# FLYTE-v1.net
KiCad netlist of a schematic drawn in EAGLE
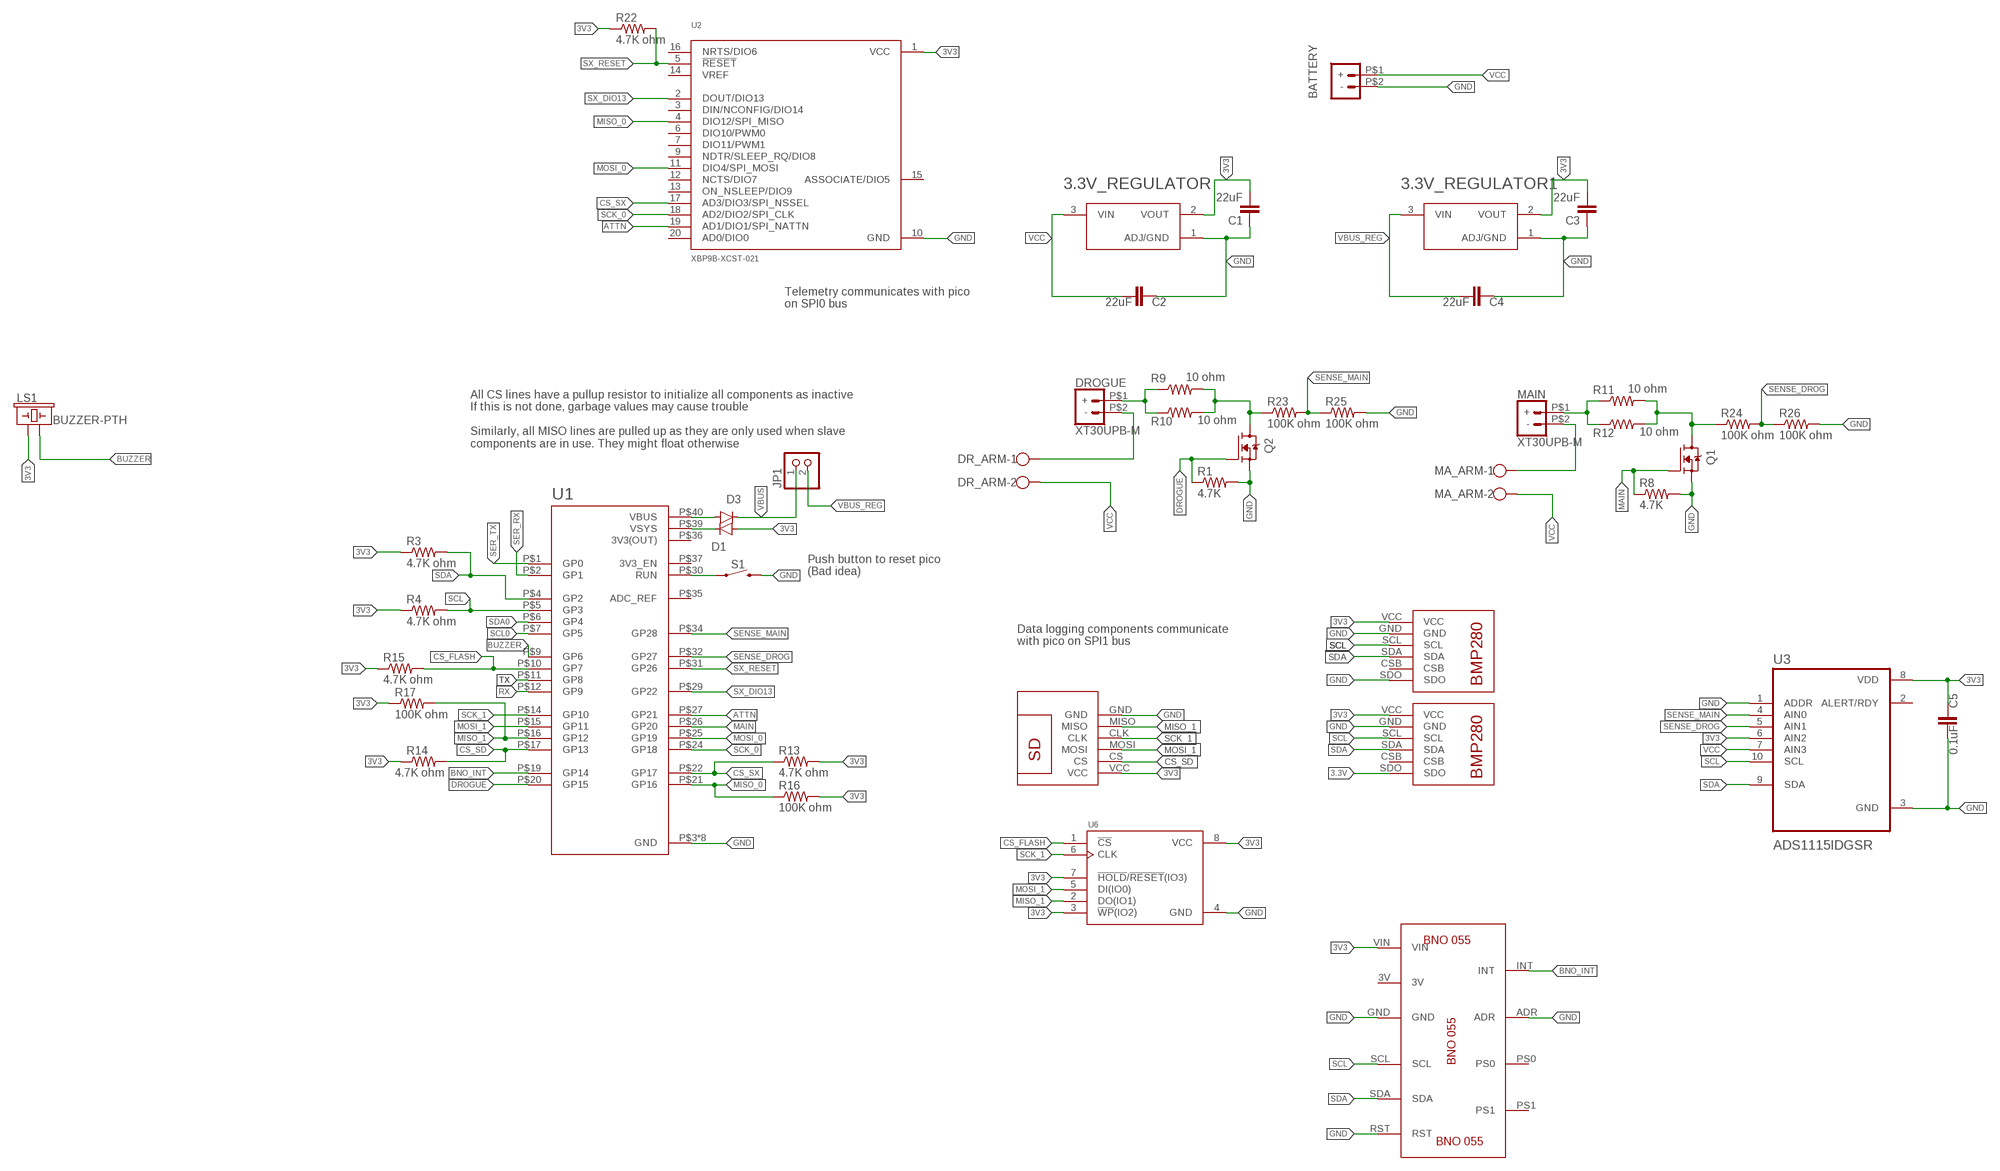
[diagram p0: schematic, sheet 1]

(export (version "E")
  (design (tool "Eeschema 10.0.6"))
  (components
    (comp (ref "3.3V_REGULATOR")
      (value "AMS1117-3.3")
      (footprint "eagle-import:SOT229P700X180-4N")
      (fields (field (name "MF") "Advanced Monolithic Systems"))
      (libsource (lib "eagle-import") (part "AMS1117-3.3"))
    )
    (comp (ref "3.3V_REGULATOR1")
      (value "AMS1117-3.3")
      (footprint "eagle-import:SOT229P700X180-4N")
      (fields (field (name "MF") "Advanced Monolithic Systems"))
      (libsource (lib "eagle-import") (part "AMS1117-3.3"))
    )
    (comp (ref "BATTERY")
      (value "XT30UPB-M")
      (footprint "eagle-import:XT30UPB-M")
      (fields (field (name "MF") "amass"))
      (libsource (lib "eagle-import") (part "XT30UPB-M"))
    )
    (comp (ref "C1")
      (value "22uF")
      (footprint "eagle-import:0805")
      (libsource (lib "eagle-import") (part "22UF-0805-6.3V-20%"))
    )
    (comp (ref "C2")
      (value "22uF")
      (footprint "eagle-import:0805")
      (libsource (lib "eagle-import") (part "22UF-0805-6.3V-20%"))
    )
    (comp (ref "C3")
      (value "22uF")
      (footprint "eagle-import:0805")
      (libsource (lib "eagle-import") (part "22UF-0805-6.3V-20%"))
    )
    (comp (ref "C4")
      (value "22uF")
      (footprint "eagle-import:0805")
      (libsource (lib "eagle-import") (part "22UF-0805-6.3V-20%"))
    )
    (comp (ref "C5")
      (value "0.1uF")
      (footprint "eagle-import:0805")
      (libsource (lib "eagle-import") (part "22UF-0805-6.3V-20%"))
    )
    (comp (ref "D1")
      (value "1N4004")
      (footprint "eagle-import:DO41-10")
      (libsource (lib "eagle-import") (part "1N4004"))
    )
    (comp (ref "D3")
      (value "1N4004")
      (footprint "eagle-import:DO41-10")
      (libsource (lib "eagle-import") (part "1N4004"))
    )
    (comp (ref "DROGUE")
      (value "XT30UPB-M")
      (footprint "eagle-import:XT30UPB-M")
      (fields (field (name "MF") "amass"))
      (libsource (lib "eagle-import") (part "XT30UPB-M"))
    )
    (comp (ref "DR_ARM")
      (value "W237-102")
      (footprint "eagle-import:W237-102")
      (fields (field (name "MPN") "237-102"))
      (libsource (lib "eagle-import") (part "W237-102"))
    )
    (comp (ref "JP1")
      (value "PINHD-1X2")
      (footprint "eagle-import:1X02")
      (libsource (lib "eagle-import") (part "PINHD-1X2"))
    )
    (comp (ref "LS1")
      (value "BUZZER-PTH")
      (footprint "eagle-import:BUZZER-12MM")
      (libsource (lib "eagle-import") (part "BUZZER-PTH"))
    )
    (comp (ref "MAIN")
      (value "XT30UPB-M")
      (footprint "eagle-import:XT30UPB-M")
      (fields (field (name "MF") "amass"))
      (libsource (lib "eagle-import") (part "XT30UPB-M"))
    )
    (comp (ref "MA_ARM")
      (value "W237-102")
      (footprint "eagle-import:W237-102")
      (fields (field (name "MPN") "237-102"))
      (libsource (lib "eagle-import") (part "W237-102"))
    )
    (comp (ref "Q1")
      (value "IRF540NPBF")
      (footprint "eagle-import:TO254P1054X469X1930-3")
      (fields (field (name "MF") "Infineon"))
      (libsource (lib "eagle-import") (part "IRF540NPBF"))
    )
    (comp (ref "Q2")
      (value "IRF540NPBF")
      (footprint "eagle-import:TO254P1054X469X1930-3")
      (fields (field (name "MF") "Infineon"))
      (libsource (lib "eagle-import") (part "IRF540NPBF"))
    )
    (comp (ref "R1")
      (value "4.7K")
      (footprint "eagle-import:R0805")
      (libsource (lib "eagle-import") (part "R-US_R0805"))
    )
    (comp (ref "R3")
      (value "4.7K ohm")
      (footprint "eagle-import:R0805")
      (libsource (lib "eagle-import") (part "R-US_R0805"))
    )
    (comp (ref "R4")
      (value "4.7K ohm")
      (footprint "eagle-import:R0805")
      (libsource (lib "eagle-import") (part "R-US_R0805"))
    )
    (comp (ref "R8")
      (value "4.7K")
      (footprint "eagle-import:R0805")
      (libsource (lib "eagle-import") (part "R-US_R0805"))
    )
    (comp (ref "R9")
      (value "10 ohm")
      (footprint "eagle-import:0207_10")
      (libsource (lib "eagle-import") (part "R-US_0207/10"))
    )
    (comp (ref "R10")
      (value "10 ohm")
      (footprint "eagle-import:0207_10")
      (libsource (lib "eagle-import") (part "R-US_0207/10"))
    )
    (comp (ref "R11")
      (value "10 ohm")
      (footprint "eagle-import:0207_10")
      (libsource (lib "eagle-import") (part "R-US_0207/10"))
    )
    (comp (ref "R12")
      (value "10 ohm")
      (footprint "eagle-import:0207_10")
      (libsource (lib "eagle-import") (part "R-US_0207/10"))
    )
    (comp (ref "R13")
      (value "4.7K ohm")
      (footprint "eagle-import:R0805")
      (libsource (lib "eagle-import") (part "R-US_R0805"))
    )
    (comp (ref "R14")
      (value "4.7K ohm")
      (footprint "eagle-import:R0805")
      (libsource (lib "eagle-import") (part "R-US_R0805"))
    )
    (comp (ref "R15")
      (value "4.7K ohm")
      (footprint "eagle-import:R0805")
      (libsource (lib "eagle-import") (part "R-US_R0805"))
    )
    (comp (ref "R16")
      (value "100K ohm")
      (footprint "eagle-import:R0805")
      (libsource (lib "eagle-import") (part "R-US_R0805"))
    )
    (comp (ref "R17")
      (value "100K ohm")
      (footprint "eagle-import:R0805")
      (libsource (lib "eagle-import") (part "R-US_R0805"))
    )
    (comp (ref "R22")
      (value "4.7K ohm")
      (footprint "eagle-import:R0805")
      (libsource (lib "eagle-import") (part "R-US_R0805"))
    )
    (comp (ref "R23")
      (value "100K ohm")
      (footprint "eagle-import:R0805")
      (libsource (lib "eagle-import") (part "R-US_R0805"))
    )
    (comp (ref "R24")
      (value "100K ohm")
      (footprint "eagle-import:R0805")
      (libsource (lib "eagle-import") (part "R-US_R0805"))
    )
    (comp (ref "R25")
      (value "100K ohm")
      (footprint "eagle-import:R0805")
      (libsource (lib "eagle-import") (part "R-US_R0805"))
    )
    (comp (ref "R26")
      (value "100K ohm")
      (footprint "eagle-import:R0805")
      (libsource (lib "eagle-import") (part "R-US_R0805"))
    )
    (comp (ref "S1")
      (value "MOMENTARY-SWITCH-SPST-PTH-6.0MM")
      (footprint "eagle-import:TACTILE_SWITCH_PTH_6.0MM")
      (libsource (lib "eagle-import") (part "MOMENTARY-SWITCH-SPST-PTH-6.0MM"))
    )
    (comp (ref "U$1")
      (value "BMP280")
      (footprint "eagle-import:BMP280")
      (libsource (lib "eagle-import") (part "BMP280"))
    )
    (comp (ref "U$2")
      (value "BMP280")
      (footprint "eagle-import:BMP280")
      (libsource (lib "eagle-import") (part "BMP280"))
    )
    (comp (ref "U$3")
      (value "SDREADER")
      (footprint "eagle-import:SDREADER")
      (libsource (lib "eagle-import") (part "SDREADER"))
    )
    (comp (ref "U$4")
      (value "BNO055")
      (footprint "eagle-import:BNO055")
      (libsource (lib "eagle-import") (part "BNO055"))
    )
    (comp (ref "U1")
      (value "RASPBERRY_PICO-NO_DEBUG")
      (footprint "eagle-import:PICO-PKG-NO_DEBUG")
      (libsource (lib "eagle-import") (part "RASPBERRY_PICO-NO_DEBUG"))
    )
    (comp (ref "U2")
      (value "XBP9B-XCST-021")
      (footprint "eagle-import:DIP2200W51P200L3294H279Q20P")
      (fields (field (name "MF") "Digi International"))
      (libsource (lib "eagle-import") (part "XBP9B-XCST-021"))
    )
    (comp (ref "U3")
      (value "ADS1115IDGSR")
      (footprint "eagle-import:SOP50P490X110-10N")
      (fields (field (name "MF") "Texas Instruments"))
      (libsource (lib "eagle-import") (part "ADS1115IDGSR"))
    )
    (comp (ref "U6")
      (value "W25Q32JVSSIQ")
      (footprint "eagle-import:SOIC127P790X216-8N")
      (fields (field (name "MF") "Winbond"))
      (libsource (lib "eagle-import") (part "W25Q32JVSSIQ"))
    )
  )
  (nets
    (net (code "1") (name "/3V3(OUT)") (class "Default")
      (node (ref "U1") (pin "P$36") (pinfunction "3V3(OUT)_P$36") (pintype "power_in"))
    )
    (net (code "2") (name "3.3V") (class "Default")
      (node (ref "U$2") (pin "SDO") (pinfunction "SDO_SDO") (pintype "bidirectional"))
    )
    (net (code "3") (name "3V3") (class "Default")
      (node (ref "3.3V_REGULATOR") (pin "2") (pinfunction "VOUT_2") (pintype "output"))
      (node (ref "3.3V_REGULATOR1") (pin "2") (pinfunction "VOUT_2") (pintype "output"))
      (node (ref "C1") (pin "2") (pinfunction "2_2") (pintype "passive"))
      (node (ref "C3") (pin "2") (pinfunction "2_2") (pintype "passive"))
      (node (ref "C5") (pin "1") (pinfunction "1_1") (pintype "passive"))
      (node (ref "D1") (pin "A") (pinfunction "A_A") (pintype "passive"))
      (node (ref "LS1") (pin "+") (pinfunction "1_+") (pintype "passive"))
      (node (ref "R13") (pin "2") (pinfunction "2_2") (pintype "passive"))
      (node (ref "R14") (pin "1") (pinfunction "1_1") (pintype "passive"))
      (node (ref "R15") (pin "1") (pinfunction "1_1") (pintype "passive"))
      (node (ref "R16") (pin "2") (pinfunction "2_2") (pintype "passive"))
      (node (ref "R17") (pin "1") (pinfunction "1_1") (pintype "passive"))
      (node (ref "R22") (pin "1") (pinfunction "1_1") (pintype "passive"))
      (node (ref "R3") (pin "1") (pinfunction "1_1") (pintype "passive"))
      (node (ref "R4") (pin "1") (pinfunction "1_1") (pintype "passive"))
      (node (ref "U$1") (pin "VCC") (pinfunction "VCC_VCC") (pintype "bidirectional"))
      (node (ref "U$2") (pin "VCC") (pinfunction "VCC_VCC") (pintype "bidirectional"))
      (node (ref "U$3") (pin "VCC") (pinfunction "VCC_VCC") (pintype "bidirectional"))
      (node (ref "U$4") (pin "VIN") (pinfunction "VIN_VIN") (pintype "bidirectional"))
      (node (ref "U2") (pin "1") (pinfunction "VCC_1") (pintype "power_in"))
      (node (ref "U3") (pin "6") (pinfunction "AIN2_6") (pintype "input"))
      (node (ref "U3") (pin "8") (pinfunction "VDD_8") (pintype "power_in"))
      (node (ref "U6") (pin "3") (pinfunction "~{WP}(IO2)_3") (pintype "bidirectional"))
      (node (ref "U6") (pin "7") (pinfunction "~{HOLD}/~{RESET}(IO3)_7") (pintype "bidirectional"))
      (node (ref "U6") (pin "8") (pinfunction "VCC_8") (pintype "power_in"))
    )
    (net (code "4") (name "ATTN") (class "Default")
      (node (ref "U1") (pin "P$27") (pinfunction "GP21_P$27") (pintype "bidirectional"))
      (node (ref "U2") (pin "19") (pinfunction "AD1/DIO1/SPI_NATTN_19") (pintype "bidirectional"))
    )
    (net (code "5") (name "BNO_INT") (class "Default")
      (node (ref "U$4") (pin "INT") (pinfunction "INT_INT") (pintype "bidirectional"))
      (node (ref "U1") (pin "P$19") (pinfunction "GP14_P$19") (pintype "bidirectional"))
    )
    (net (code "6") (name "BUZZER") (class "Default")
      (node (ref "LS1") (pin "-") (pinfunction "2_-") (pintype "passive"))
      (node (ref "U1") (pin "P$9") (pinfunction "GP6_P$9") (pintype "bidirectional"))
    )
    (net (code "7") (name "CS_FLASH") (class "Default")
      (node (ref "R15") (pin "2") (pinfunction "2_2") (pintype "passive"))
      (node (ref "U1") (pin "P$10") (pinfunction "GP7_P$10") (pintype "bidirectional"))
      (node (ref "U6") (pin "1") (pinfunction "~{CS}_1") (pintype "input"))
    )
    (net (code "8") (name "CS_SD") (class "Default")
      (node (ref "R14") (pin "2") (pinfunction "2_2") (pintype "passive"))
      (node (ref "U$3") (pin "CS") (pinfunction "CS_CS") (pintype "bidirectional"))
      (node (ref "U1") (pin "P$17") (pinfunction "GP13_P$17") (pintype "bidirectional"))
    )
    (net (code "9") (name "CS_SX") (class "Default")
      (node (ref "R13") (pin "1") (pinfunction "1_1") (pintype "passive"))
      (node (ref "U1") (pin "P$22") (pinfunction "GP17_P$22") (pintype "bidirectional"))
      (node (ref "U2") (pin "17") (pinfunction "AD3/DIO3/SPI_NSSEL_17") (pintype "bidirectional"))
    )
    (net (code "10") (name "DROGUE") (class "Default")
      (node (ref "Q2") (pin "1") (pinfunction "G_1") (pintype "passive"))
      (node (ref "R1") (pin "1") (pinfunction "1_1") (pintype "passive"))
      (node (ref "U1") (pin "P$20") (pinfunction "GP15_P$20") (pintype "bidirectional"))
    )
    (net (code "11") (name "GND") (class "Default")
      (node (ref "3.3V_REGULATOR") (pin "1") (pinfunction "ADJ/GND_1") (pintype "power_in"))
      (node (ref "3.3V_REGULATOR1") (pin "1") (pinfunction "ADJ/GND_1") (pintype "power_in"))
      (node (ref "BATTERY") (pin "P$2") (pinfunction "-_P$2") (pintype "passive"))
      (node (ref "C1") (pin "1") (pinfunction "1_1") (pintype "passive"))
      (node (ref "C2") (pin "1") (pinfunction "1_1") (pintype "passive"))
      (node (ref "C3") (pin "1") (pinfunction "1_1") (pintype "passive"))
      (node (ref "C4") (pin "1") (pinfunction "1_1") (pintype "passive"))
      (node (ref "C5") (pin "2") (pinfunction "2_2") (pintype "passive"))
      (node (ref "Q1") (pin "3") (pinfunction "S_3") (pintype "passive"))
      (node (ref "Q2") (pin "3") (pinfunction "S_3") (pintype "passive"))
      (node (ref "R1") (pin "2") (pinfunction "2_2") (pintype "passive"))
      (node (ref "R25") (pin "2") (pinfunction "2_2") (pintype "passive"))
      (node (ref "R26") (pin "2") (pinfunction "2_2") (pintype "passive"))
      (node (ref "R8") (pin "2") (pinfunction "2_2") (pintype "passive"))
      (node (ref "S1") (pin "3") (pinfunction "2_3") (pintype "passive"))
      (node (ref "U$1") (pin "GND") (pinfunction "GND_GND") (pintype "bidirectional"))
      (node (ref "U$1") (pin "SDO") (pinfunction "SDO_SDO") (pintype "bidirectional"))
      (node (ref "U$2") (pin "GND") (pinfunction "GND_GND") (pintype "bidirectional"))
      (node (ref "U$3") (pin "GND") (pinfunction "GND_GND") (pintype "bidirectional"))
      (node (ref "U$4") (pin "ADR") (pinfunction "ADR_ADR") (pintype "bidirectional"))
      (node (ref "U$4") (pin "GND") (pinfunction "GND_GND") (pintype "bidirectional"))
      (node (ref "U$4") (pin "RST") (pinfunction "RST_RST") (pintype "bidirectional"))
      (node (ref "U1") (pin "P$13") (pinfunction "GND_P$13") (pintype "power_in"))
      (node (ref "U1") (pin "P$18") (pinfunction "GND_P$18") (pintype "power_in"))
      (node (ref "U1") (pin "P$23") (pinfunction "GND_P$23") (pintype "power_in"))
      (node (ref "U1") (pin "P$28") (pinfunction "GND_P$28") (pintype "power_in"))
      (node (ref "U1") (pin "P$3") (pinfunction "GND_P$3") (pintype "power_in"))
      (node (ref "U1") (pin "P$33") (pinfunction "GND_P$33") (pintype "power_in"))
      (node (ref "U1") (pin "P$38") (pinfunction "GND_P$38") (pintype "power_in"))
      (node (ref "U1") (pin "P$8") (pinfunction "GND_P$8") (pintype "power_in"))
      (node (ref "U2") (pin "10") (pinfunction "GND_10") (pintype "power_in"))
      (node (ref "U3") (pin "1") (pinfunction "ADDR_1") (pintype "input"))
      (node (ref "U3") (pin "3") (pinfunction "GND_3") (pintype "power_in"))
      (node (ref "U6") (pin "4") (pinfunction "GND_4") (pintype "power_in"))
    )
    (net (code "12") (name "MAIN") (class "Default")
      (node (ref "Q1") (pin "1") (pinfunction "G_1") (pintype "passive"))
      (node (ref "R8") (pin "1") (pinfunction "1_1") (pintype "passive"))
      (node (ref "U1") (pin "P$26") (pinfunction "GP20_P$26") (pintype "bidirectional"))
    )
    (net (code "13") (name "MISO_0") (class "Default")
      (node (ref "R16") (pin "1") (pinfunction "1_1") (pintype "passive"))
      (node (ref "U1") (pin "P$21") (pinfunction "GP16_P$21") (pintype "bidirectional"))
      (node (ref "U2") (pin "4") (pinfunction "DIO12/SPI_MISO_4") (pintype "bidirectional"))
    )
    (net (code "14") (name "MISO_1") (class "Default")
      (node (ref "R17") (pin "2") (pinfunction "2_2") (pintype "passive"))
      (node (ref "U$3") (pin "MISO") (pinfunction "MISO_MISO") (pintype "bidirectional"))
      (node (ref "U1") (pin "P$16") (pinfunction "GP12_P$16") (pintype "bidirectional"))
      (node (ref "U6") (pin "2") (pinfunction "DO(IO1)_2") (pintype "bidirectional"))
    )
    (net (code "15") (name "MOSI_0") (class "Default")
      (node (ref "U1") (pin "P$25") (pinfunction "GP19_P$25") (pintype "bidirectional"))
      (node (ref "U2") (pin "11") (pinfunction "DIO4/SPI_MOSI_11") (pintype "bidirectional"))
    )
    (net (code "16") (name "MOSI_1") (class "Default")
      (node (ref "U$3") (pin "MOSI") (pinfunction "MOSI_MOSI") (pintype "bidirectional"))
      (node (ref "U1") (pin "P$15") (pinfunction "GP11_P$15") (pintype "bidirectional"))
      (node (ref "U6") (pin "5") (pinfunction "DI(IO0)_5") (pintype "bidirectional"))
    )
    (net (code "17") (name "Net-(DROGUE-+)") (class "Default")
      (node (ref "DROGUE") (pin "P$1") (pinfunction "+_P$1") (pintype "passive"))
      (node (ref "R10") (pin "1") (pinfunction "1_1") (pintype "passive"))
      (node (ref "R9") (pin "1") (pinfunction "1_1") (pintype "passive"))
    )
    (net (code "18") (name "Net-(DROGUE--)") (class "Default")
      (node (ref "DROGUE") (pin "P$2") (pinfunction "-_P$2") (pintype "passive"))
      (node (ref "DR_ARM") (pin "1") (pinfunction "KL_1") (pintype "passive"))
    )
    (net (code "19") (name "Net-(MAIN-+)") (class "Default")
      (node (ref "MAIN") (pin "P$1") (pinfunction "+_P$1") (pintype "passive"))
      (node (ref "R11") (pin "1") (pinfunction "1_1") (pintype "passive"))
      (node (ref "R12") (pin "1") (pinfunction "1_1") (pintype "passive"))
    )
    (net (code "20") (name "Net-(MAIN--)") (class "Default")
      (node (ref "MAIN") (pin "P$2") (pinfunction "-_P$2") (pintype "passive"))
      (node (ref "MA_ARM") (pin "1") (pinfunction "KL_1") (pintype "passive"))
    )
    (net (code "21") (name "Net-(Q1-D)") (class "Default")
      (node (ref "Q1") (pin "2") (pinfunction "D_2") (pintype "passive"))
      (node (ref "R11") (pin "2") (pinfunction "2_2") (pintype "passive"))
      (node (ref "R12") (pin "2") (pinfunction "2_2") (pintype "passive"))
      (node (ref "R24") (pin "1") (pinfunction "1_1") (pintype "passive"))
    )
    (net (code "22") (name "Net-(Q2-D)") (class "Default")
      (node (ref "Q2") (pin "2") (pinfunction "D_2") (pintype "passive"))
      (node (ref "R10") (pin "2") (pinfunction "2_2") (pintype "passive"))
      (node (ref "R23") (pin "1") (pinfunction "1_1") (pintype "passive"))
      (node (ref "R9") (pin "2") (pinfunction "2_2") (pintype "passive"))
    )
    (net (code "23") (name "Net-(U1-RUN)") (class "Default")
      (node (ref "S1") (pin "1") (pinfunction "1_1") (pintype "passive"))
      (node (ref "U1") (pin "P$30") (pinfunction "RUN_P$30") (pintype "input"))
    )
    (net (code "24") (name "Net-(U1-VBUS)") (class "Default")
      (node (ref "D3") (pin "A") (pinfunction "A_A") (pintype "passive"))
      (node (ref "U1") (pin "P$40") (pinfunction "VBUS_P$40") (pintype "power_in"))
    )
    (net (code "25") (name "Net-(U1-VSYS)") (class "Default")
      (node (ref "D1") (pin "C") (pinfunction "C_C") (pintype "passive"))
      (node (ref "U1") (pin "P$39") (pinfunction "VSYS_P$39") (pintype "power_in"))
    )
    (net (code "26") (name "RX") (class "Default")
      (node (ref "U1") (pin "P$12") (pinfunction "GP9_P$12") (pintype "bidirectional"))
    )
    (net (code "27") (name "SCK_0") (class "Default")
      (node (ref "U1") (pin "P$24") (pinfunction "GP18_P$24") (pintype "bidirectional"))
      (node (ref "U2") (pin "18") (pinfunction "AD2/DIO2/SPI_CLK_18") (pintype "bidirectional"))
    )
    (net (code "28") (name "SCK_1") (class "Default")
      (node (ref "U$3") (pin "CLK") (pinfunction "CLK_CLK") (pintype "bidirectional"))
      (node (ref "U1") (pin "P$14") (pinfunction "GP10_P$14") (pintype "bidirectional"))
      (node (ref "U6") (pin "6") (pinfunction "CLK_6") (pintype "input"))
    )
    (net (code "29") (name "SCL") (class "Default")
      (node (ref "R4") (pin "2") (pinfunction "2_2") (pintype "passive"))
      (node (ref "U$1") (pin "SCL") (pinfunction "SCL_SCL") (pintype "bidirectional"))
      (node (ref "U$2") (pin "SCL") (pinfunction "SCL_SCL") (pintype "bidirectional"))
      (node (ref "U$4") (pin "SCL") (pinfunction "SCL_SCL") (pintype "bidirectional"))
      (node (ref "U1") (pin "P$5") (pinfunction "GP3_P$5") (pintype "bidirectional"))
      (node (ref "U3") (pin "10") (pinfunction "SCL_10") (pintype "input"))
    )
    (net (code "30") (name "SCL0") (class "Default")
      (node (ref "U1") (pin "P$7") (pinfunction "GP5_P$7") (pintype "bidirectional"))
    )
    (net (code "31") (name "SDA") (class "Default")
      (node (ref "R3") (pin "2") (pinfunction "2_2") (pintype "passive"))
      (node (ref "U$1") (pin "SDA") (pinfunction "SDA_SDA") (pintype "bidirectional"))
      (node (ref "U$2") (pin "SDA") (pinfunction "SDA_SDA") (pintype "bidirectional"))
      (node (ref "U$4") (pin "SDA") (pinfunction "SDA_SDA") (pintype "bidirectional"))
      (node (ref "U1") (pin "P$4") (pinfunction "GP2_P$4") (pintype "bidirectional"))
      (node (ref "U3") (pin "9") (pinfunction "SDA_9") (pintype "bidirectional"))
    )
    (net (code "32") (name "SDA0") (class "Default")
      (node (ref "U1") (pin "P$6") (pinfunction "GP4_P$6") (pintype "bidirectional"))
    )
    (net (code "33") (name "SENSE_DROG") (class "Default")
      (node (ref "R24") (pin "2") (pinfunction "2_2") (pintype "passive"))
      (node (ref "R26") (pin "1") (pinfunction "1_1") (pintype "passive"))
      (node (ref "U1") (pin "P$32") (pinfunction "GP27_P$32") (pintype "bidirectional"))
      (node (ref "U3") (pin "5") (pinfunction "AIN1_5") (pintype "input"))
    )
    (net (code "34") (name "SENSE_MAIN") (class "Default")
      (node (ref "R23") (pin "2") (pinfunction "2_2") (pintype "passive"))
      (node (ref "R25") (pin "1") (pinfunction "1_1") (pintype "passive"))
      (node (ref "U1") (pin "P$34") (pinfunction "GP28_P$34") (pintype "bidirectional"))
      (node (ref "U3") (pin "4") (pinfunction "AIN0_4") (pintype "input"))
    )
    (net (code "35") (name "SER_RX") (class "Default")
      (node (ref "U1") (pin "P$2") (pinfunction "GP1_P$2") (pintype "bidirectional"))
    )
    (net (code "36") (name "SER_TX") (class "Default")
      (node (ref "U1") (pin "P$1") (pinfunction "GP0_P$1") (pintype "bidirectional"))
    )
    (net (code "37") (name "SX_DIO13") (class "Default")
      (node (ref "U1") (pin "P$29") (pinfunction "GP22_P$29") (pintype "bidirectional"))
      (node (ref "U2") (pin "2") (pinfunction "DOUT/DIO13_2") (pintype "bidirectional"))
    )
    (net (code "38") (name "SX_RESET") (class "Default")
      (node (ref "R22") (pin "2") (pinfunction "2_2") (pintype "passive"))
      (node (ref "U1") (pin "P$31") (pinfunction "GP26_P$31") (pintype "bidirectional"))
      (node (ref "U2") (pin "5") (pinfunction "~{RESET}_5") (pintype "input"))
    )
    (net (code "39") (name "TX") (class "Default")
      (node (ref "U1") (pin "P$11") (pinfunction "GP8_P$11") (pintype "bidirectional"))
    )
    (net (code "40") (name "VBUS") (class "Default")
      (node (ref "D3") (pin "C") (pinfunction "C_C") (pintype "passive"))
      (node (ref "JP1") (pin "1") (pinfunction "1_1") (pintype "passive"))
    )
    (net (code "41") (name "VBUS_REG") (class "Default")
      (node (ref "3.3V_REGULATOR1") (pin "3") (pinfunction "VIN_3") (pintype "input"))
      (node (ref "C4") (pin "2") (pinfunction "2_2") (pintype "passive"))
      (node (ref "JP1") (pin "2") (pinfunction "2_2") (pintype "passive"))
    )
    (net (code "42") (name "VCC") (class "Default")
      (node (ref "3.3V_REGULATOR") (pin "3") (pinfunction "VIN_3") (pintype "input"))
      (node (ref "BATTERY") (pin "P$1") (pinfunction "+_P$1") (pintype "passive"))
      (node (ref "C2") (pin "2") (pinfunction "2_2") (pintype "passive"))
      (node (ref "DR_ARM") (pin "2") (pinfunction "KL_2") (pintype "passive"))
      (node (ref "MA_ARM") (pin "2") (pinfunction "KL_2") (pintype "passive"))
      (node (ref "U3") (pin "7") (pinfunction "AIN3_7") (pintype "input"))
    )
    (net (code "43") (name "unconnected-(U$1-PadCSB)") (class "Default")
      (node (ref "U$1") (pin "CSB") (pinfunction "CSB_CSB") (pintype "bidirectional"))
    )
    (net (code "44") (name "unconnected-(U$2-PadCSB)") (class "Default")
      (node (ref "U$2") (pin "CSB") (pinfunction "CSB_CSB") (pintype "bidirectional"))
    )
    (net (code "45") (name "unconnected-(U$4-Pad3V)") (class "Default")
      (node (ref "U$4") (pin "3V") (pinfunction "3V_3V") (pintype "bidirectional"))
    )
    (net (code "46") (name "unconnected-(U$4-PadPS0)") (class "Default")
      (node (ref "U$4") (pin "PS0") (pinfunction "PS0_PS0") (pintype "bidirectional"))
    )
    (net (code "47") (name "unconnected-(U$4-PadPS1)") (class "Default")
      (node (ref "U$4") (pin "PS1") (pinfunction "PS1_PS1") (pintype "bidirectional"))
    )
    (net (code "48") (name "unconnected-(U1-3V3_EN-PadP$37)") (class "Default")
      (node (ref "U1") (pin "P$37") (pinfunction "3V3_EN_P$37") (pintype "input"))
    )
    (net (code "49") (name "unconnected-(U1-ADC_REF-PadP$35)") (class "Default")
      (node (ref "U1") (pin "P$35") (pinfunction "ADC_REF_P$35") (pintype "input"))
    )
    (net (code "50") (name "unconnected-(U2-AD0{slash}DIO0-Pad20)") (class "Default")
      (node (ref "U2") (pin "20") (pinfunction "AD0/DIO0_20") (pintype "bidirectional"))
    )
    (net (code "51") (name "unconnected-(U2-ASSOCIATE{slash}DIO5-Pad15)") (class "Default")
      (node (ref "U2") (pin "15") (pinfunction "ASSOCIATE/DIO5_15") (pintype "output"))
    )
    (net (code "52") (name "unconnected-(U2-DIN{slash}NCONFIG{slash}DIO14-Pad3)") (class "Default")
      (node (ref "U2") (pin "3") (pinfunction "DIN/NCONFIG/DIO14_3") (pintype "bidirectional"))
    )
    (net (code "53") (name "unconnected-(U2-DIO10{slash}PWM0-Pad6)") (class "Default")
      (node (ref "U2") (pin "6") (pinfunction "DIO10/PWM0_6") (pintype "bidirectional"))
    )
    (net (code "54") (name "unconnected-(U2-DIO11{slash}PWM1-Pad7)") (class "Default")
      (node (ref "U2") (pin "7") (pinfunction "DIO11/PWM1_7") (pintype "bidirectional"))
    )
    (net (code "55") (name "unconnected-(U2-NCTS{slash}DIO7-Pad12)") (class "Default")
      (node (ref "U2") (pin "12") (pinfunction "NCTS/DIO7_12") (pintype "bidirectional"))
    )
    (net (code "56") (name "unconnected-(U2-NDTR{slash}SLEEP_RQ{slash}DIO8-Pad9)") (class "Default")
      (node (ref "U2") (pin "9") (pinfunction "NDTR/SLEEP_RQ/DIO8_9") (pintype "bidirectional"))
    )
    (net (code "57") (name "unconnected-(U2-NRTS{slash}DIO6-Pad16)") (class "Default")
      (node (ref "U2") (pin "16") (pinfunction "NRTS/DIO6_16") (pintype "input"))
    )
    (net (code "58") (name "unconnected-(U2-ON_NSLEEP{slash}DIO9-Pad13)") (class "Default")
      (node (ref "U2") (pin "13") (pinfunction "ON_NSLEEP/DIO9_13") (pintype "bidirectional"))
    )
    (net (code "59") (name "unconnected-(U2-VREF-Pad14)") (class "Default")
      (node (ref "U2") (pin "14") (pinfunction "VREF_14") (pintype "input"))
    )
    (net (code "60") (name "unconnected-(U3-ALERT{slash}RDY-Pad2)") (class "Default")
      (node (ref "U3") (pin "2") (pinfunction "ALERT/RDY_2") (pintype "output"))
    )
  )
)
